# led_driver_2.net
KiCad netlist of a schematic drawn in EAGLE
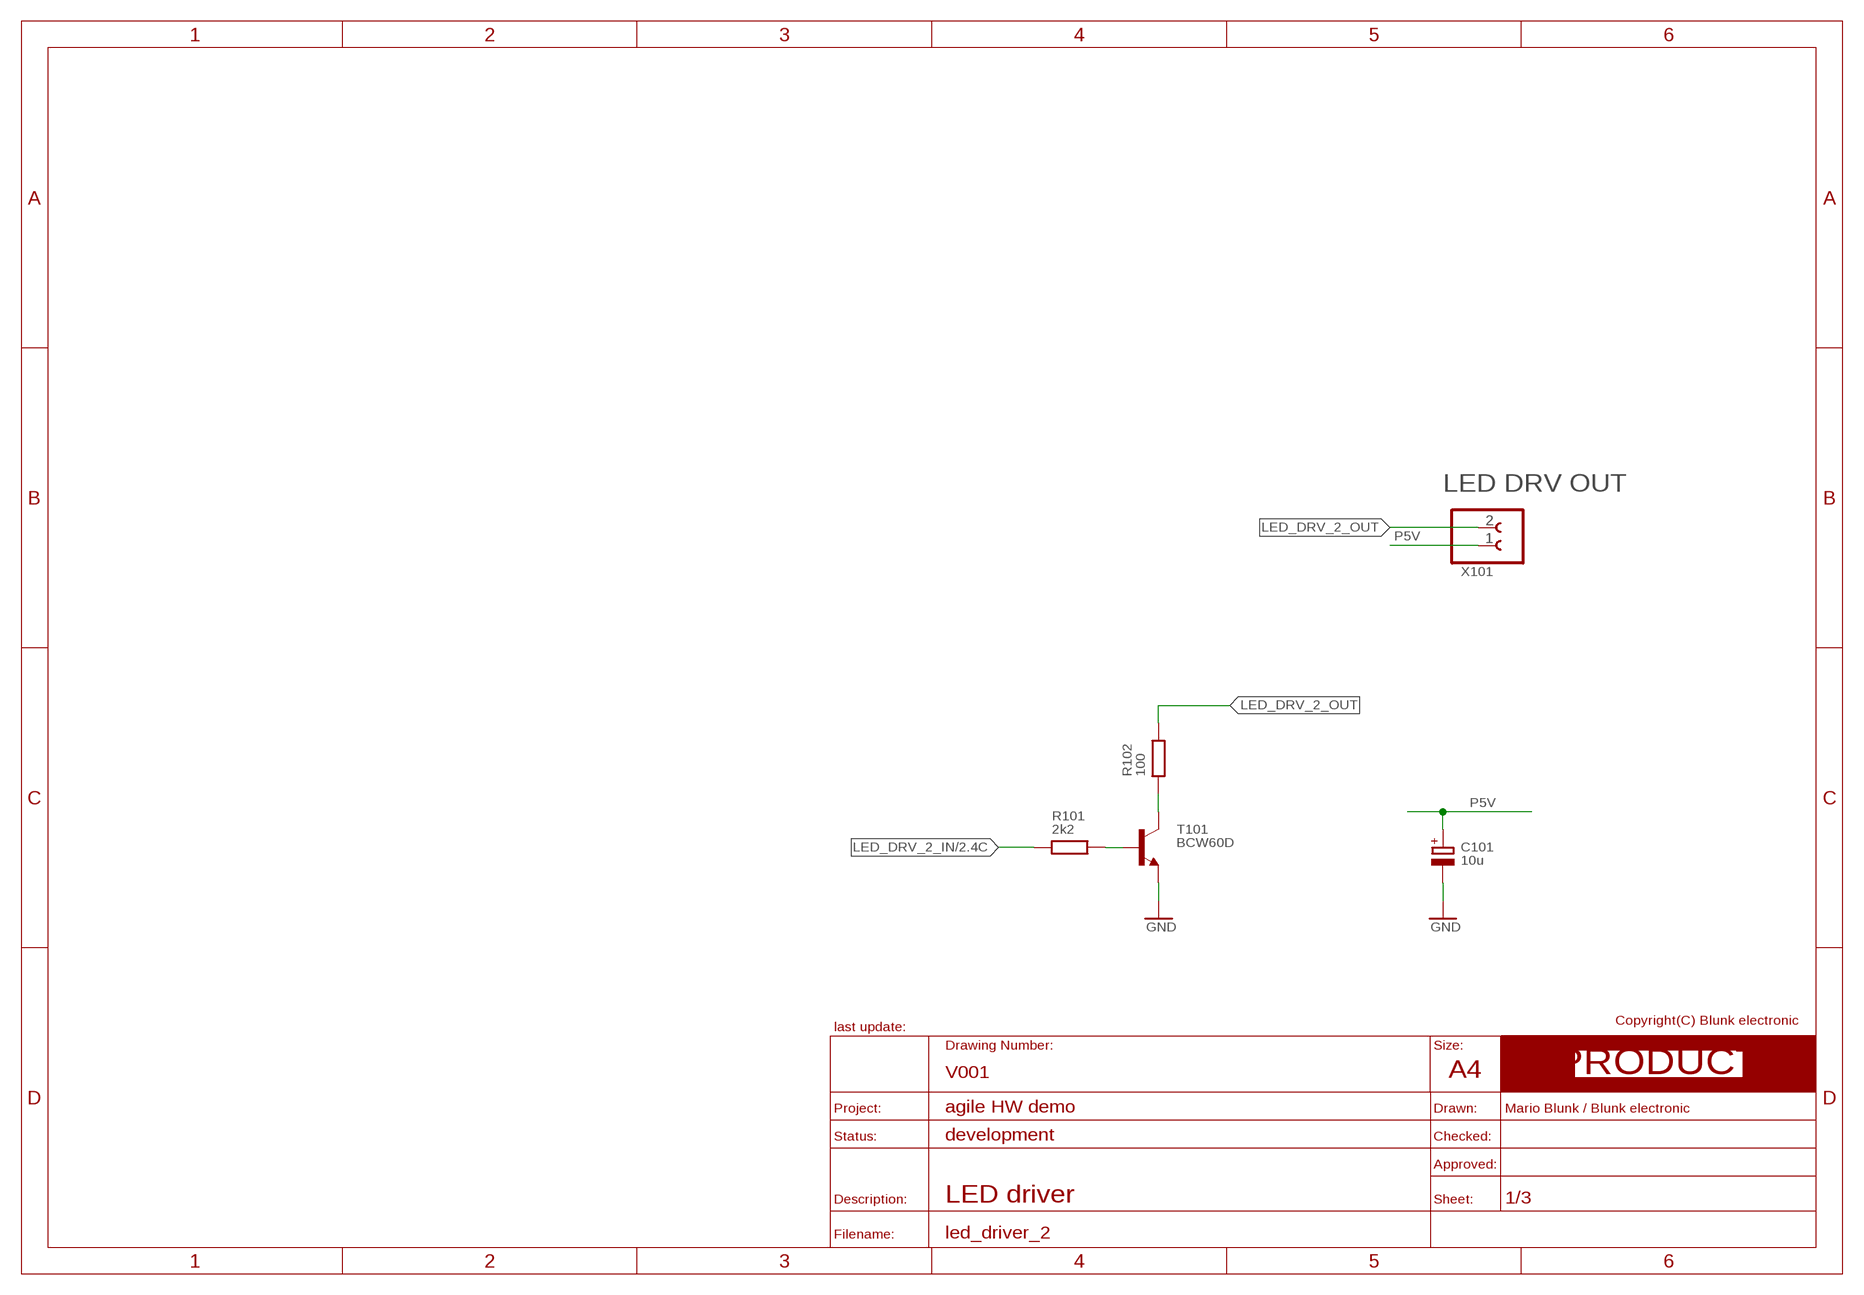
[diagram p0: schematic, sheet 1]
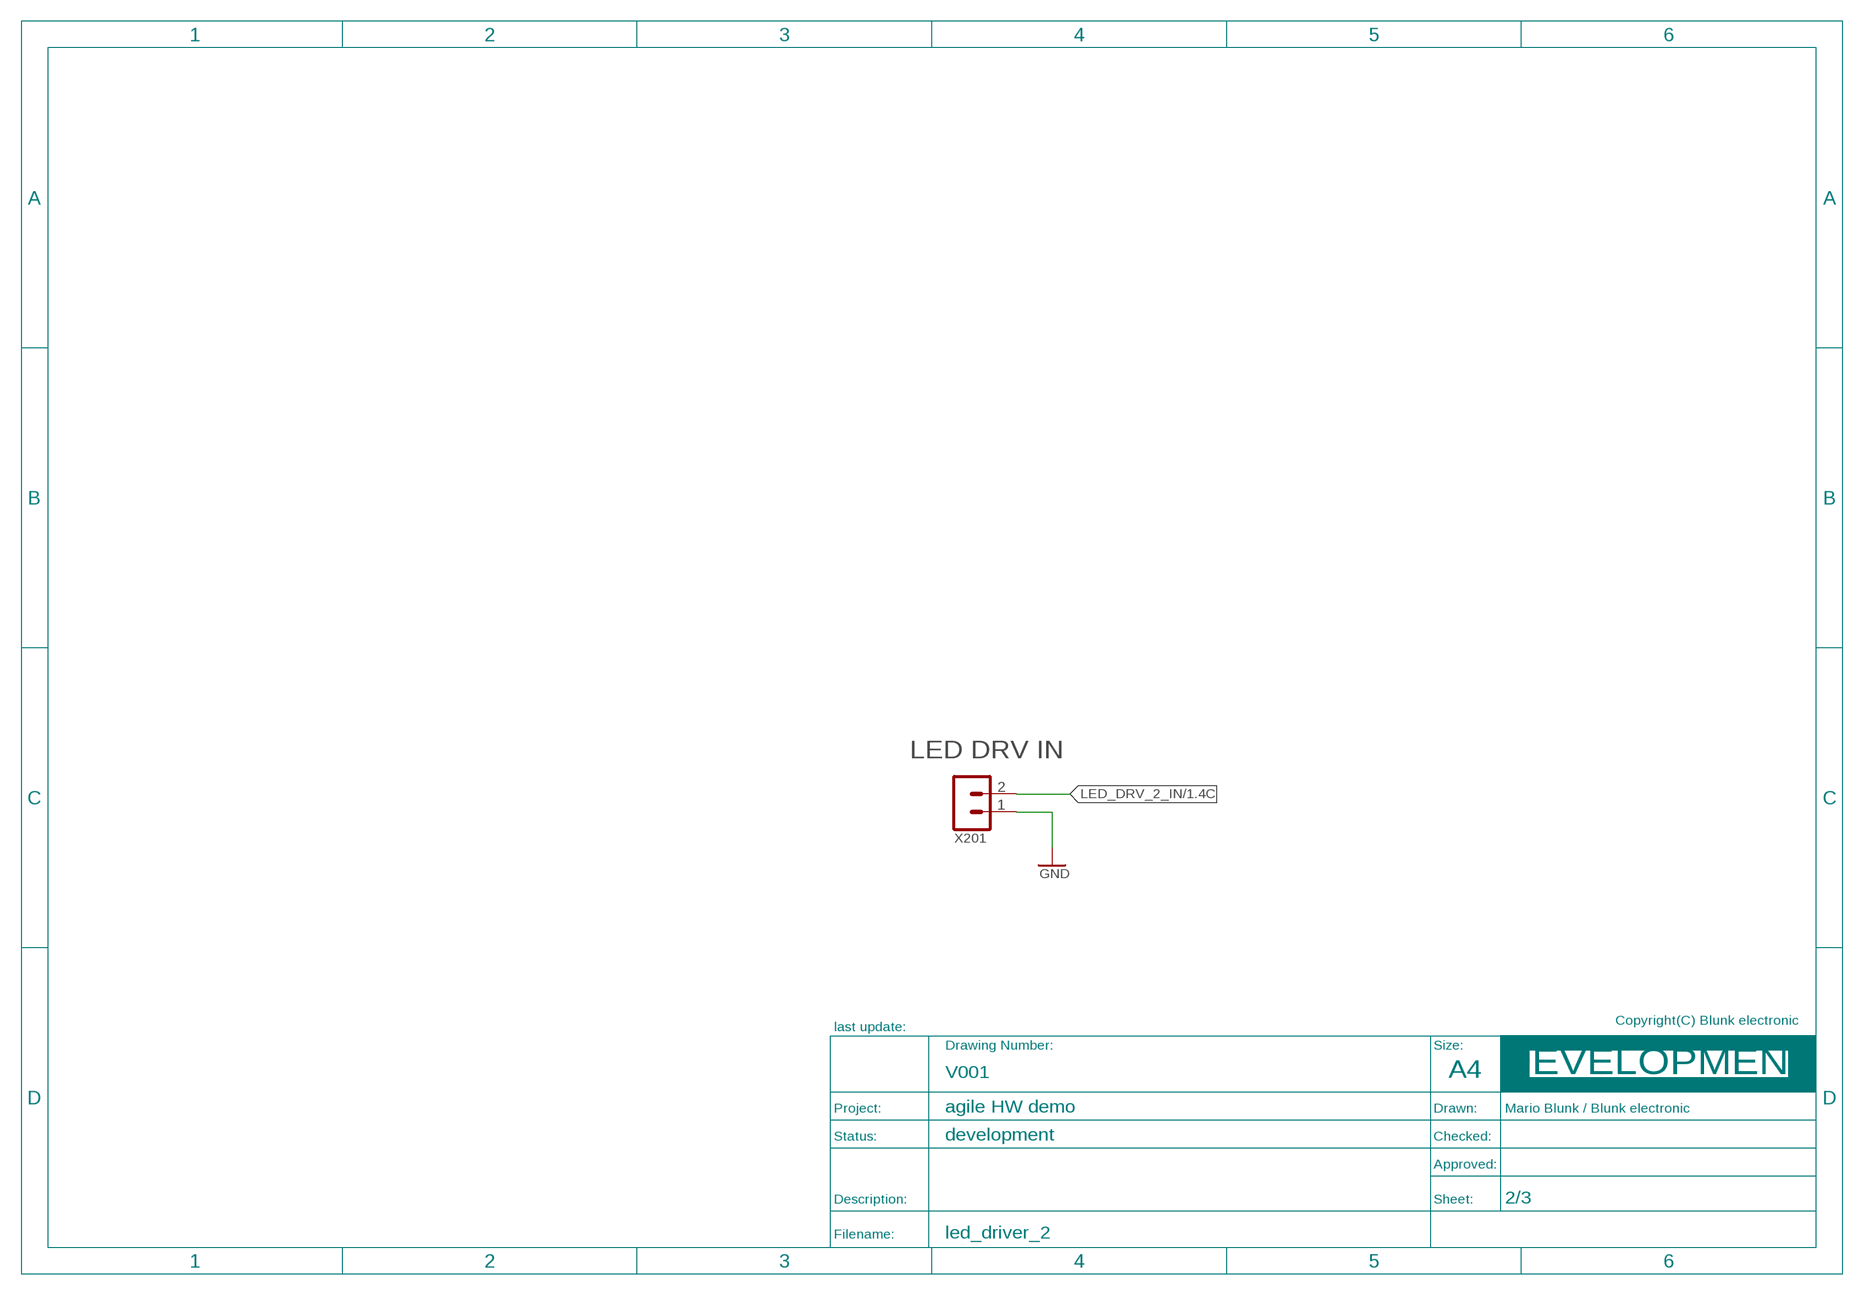
[diagram p1: schematic, sheet 2]
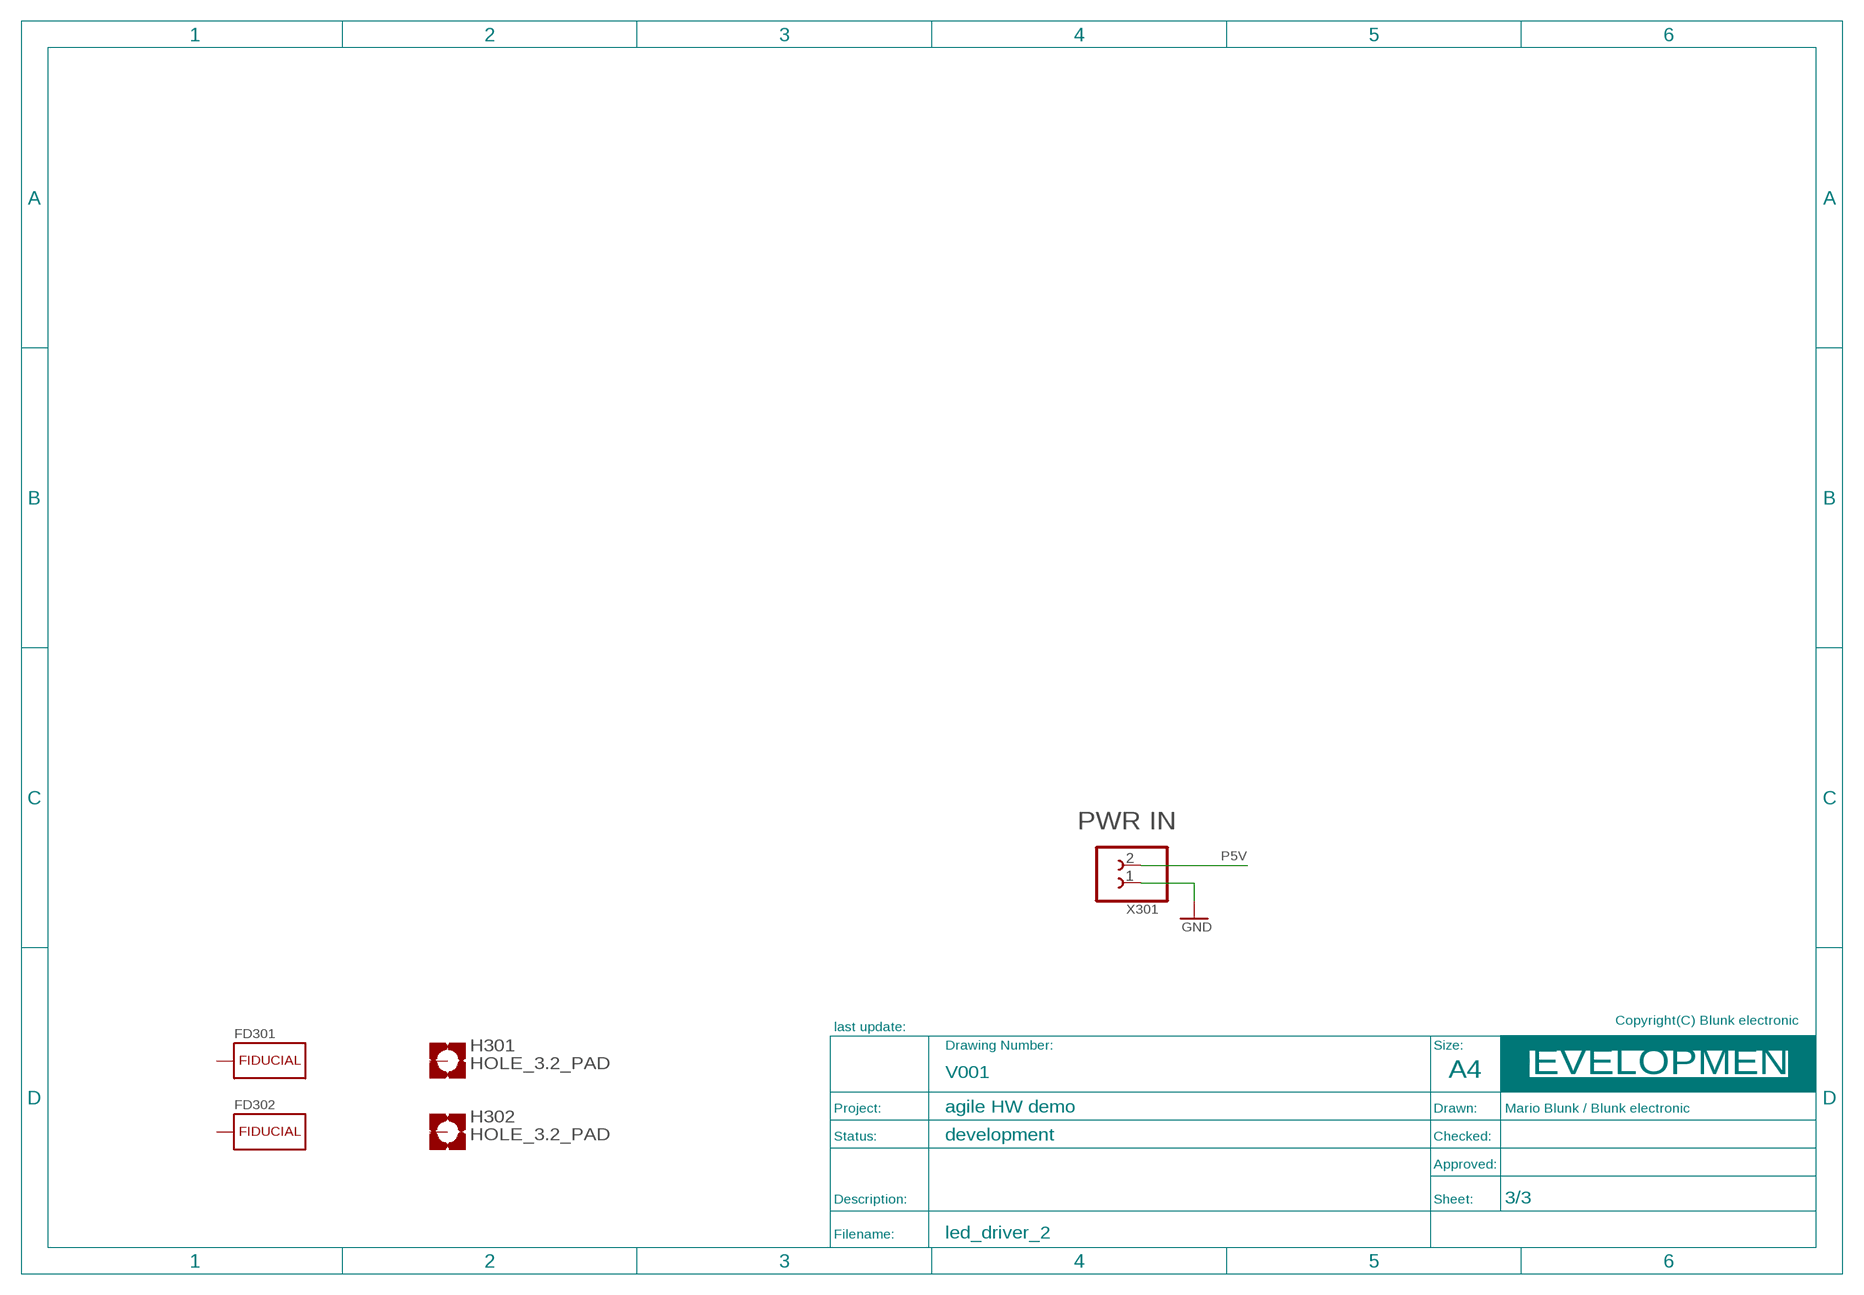
[diagram p2: schematic, sheet 3]

(export (version "E")
  (design (tool "Eeschema 10.0.6"))
  (components
    (comp (ref "C101")
      (value "10u")
      (footprint "eagle-import:S_6032")
      (fields (field (name "PART_CODE_BEL") "C_PAC_S_6032_VAL_10u_Vmax_35V"))
      (libsource (lib "eagle-import") (part "C_POL_S_6032"))
    )
    (comp (ref "R101")
      (value "2k2")
      (footprint "eagle-import:S_0805")
      (fields (field (name "PART_CODE_BEL") "R_PAC_S_0805_VAL_2k2"))
      (libsource (lib "eagle-import") (part "R_S_0805"))
    )
    (comp (ref "R102")
      (value "100")
      (footprint "eagle-import:S_0805")
      (fields (field (name "PART_CODE_BEL") "R_PAC_S_0805_VAL_100"))
      (libsource (lib "eagle-import") (part "R_S_0805"))
    )
    (comp (ref "T101")
      (value "BCW60D")
      (footprint "eagle-import:S_SOT23")
      (fields (field (name "PART_CODE_BEL") "T_PAC_S_SOT23_VAL_BCW60D"))
      (libsource (lib "eagle-import") (part "NPN_S_SOT23"))
    )
    (comp (ref "X101")
      (value "CLAMP_1X2-T-2.5MM")
      (footprint "eagle-import:T_WIRE_CLAMP_1X2_PITCH_2MM5")
      (fields (field (name "FUNCTION") "LED DRV OUT"))
      (libsource (lib "eagle-import") (part "CLAMP_1X2-T-2.5MM"))
    )
    (comp (ref "X201")
      (value "MALE_2X1-T-VERTICAL")
      (footprint "eagle-import:T_MALE_2X1_VERTICAL_PITCH_2MM54")
      (fields (field (name "FUNCTION") "LED DRV IN"))
      (libsource (lib "eagle-import") (part "MALE_2X1-T-VERTICAL"))
    )
    (comp (ref "FD301")
      (value "FIDUCIAL_CROSSHAIR")
      (footprint "eagle-import:CROSSHAIR")
      (libsource (lib "eagle-import") (part "FIDUCIAL_CROSSHAIR"))
    )
    (comp (ref "FD302")
      (value "FIDUCIAL_CROSSHAIR")
      (footprint "eagle-import:CROSSHAIR")
      (libsource (lib "eagle-import") (part "FIDUCIAL_CROSSHAIR"))
    )
    (comp (ref "H301")
      (value "HOLE_3.2_PAD")
      (footprint "eagle-import:3.2_PAD")
      (libsource (lib "eagle-import") (part "HOLE_3.2_PAD"))
    )
    (comp (ref "H302")
      (value "HOLE_3.2_PAD")
      (footprint "eagle-import:3.2_PAD")
      (libsource (lib "eagle-import") (part "HOLE_3.2_PAD"))
    )
    (comp (ref "X301")
      (value "CLAMP_1X2-T-2.5MM")
      (footprint "eagle-import:T_WIRE_CLAMP_1X2_PITCH_2MM5")
      (fields (field (name "FUNCTION") "PWR IN"))
      (libsource (lib "eagle-import") (part "CLAMP_1X2-T-2.5MM"))
    )
  )
  (nets
    (net (code "1") (name "GND") (class "Default")
      (node (ref "C101") (pin "-") (pinfunction "-_-") (pintype "passive"))
      (node (ref "T101") (pin "2") (pinfunction "E_2") (pintype "passive"))
      (node (ref "X201") (pin "1") (pinfunction "1_1") (pintype "passive"))
      (node (ref "X301") (pin "1") (pinfunction "1_1") (pintype "passive"))
    )
    (net (code "2") (name "LED_DRV_2_IN") (class "Default")
      (node (ref "R101") (pin "1") (pinfunction "1_1") (pintype "passive"))
      (node (ref "X201") (pin "2") (pinfunction "2_2") (pintype "passive"))
    )
    (net (code "3") (name "LED_DRV_2_OUT") (class "Default")
      (node (ref "R102") (pin "2") (pinfunction "2_2") (pintype "passive"))
      (node (ref "X101") (pin "2") (pinfunction "2_2") (pintype "passive"))
    )
    (net (code "4") (name "Net-(T101-B)") (class "Default")
      (node (ref "R101") (pin "2") (pinfunction "2_2") (pintype "passive"))
      (node (ref "T101") (pin "1") (pinfunction "B_1") (pintype "passive"))
    )
    (net (code "5") (name "Net-(T101-C)") (class "Default")
      (node (ref "R102") (pin "1") (pinfunction "1_1") (pintype "passive"))
      (node (ref "T101") (pin "3") (pinfunction "C_3") (pintype "passive"))
    )
    (net (code "6") (name "P5V") (class "Default")
      (node (ref "C101") (pin "+") (pinfunction "+_+") (pintype "passive"))
      (node (ref "X101") (pin "1") (pinfunction "1_1") (pintype "passive"))
      (node (ref "X301") (pin "2") (pinfunction "2_2") (pintype "passive"))
    )
    (net (code "7") (name "unconnected-(FD301-NC-Pad1)") (class "Default")
      (node (ref "FD301") (pin "1") (pinfunction "NC_1") (pintype "no_connect"))
    )
    (net (code "8") (name "unconnected-(FD302-NC-Pad1)") (class "Default")
      (node (ref "FD302") (pin "1") (pinfunction "NC_1") (pintype "no_connect"))
    )
    (net (code "9") (name "unconnected-(H301-MOUNT-PadH1)") (class "Default")
      (node (ref "H301") (pin "H1") (pinfunction "MOUNT_H1") (pintype "passive"))
    )
    (net (code "10") (name "unconnected-(H302-MOUNT-PadH1)") (class "Default")
      (node (ref "H302") (pin "H1") (pinfunction "MOUNT_H1") (pintype "passive"))
    )
  )
)
